# Power_Pos.net
KiCad netlist of a schematic drawn in Altium Designer
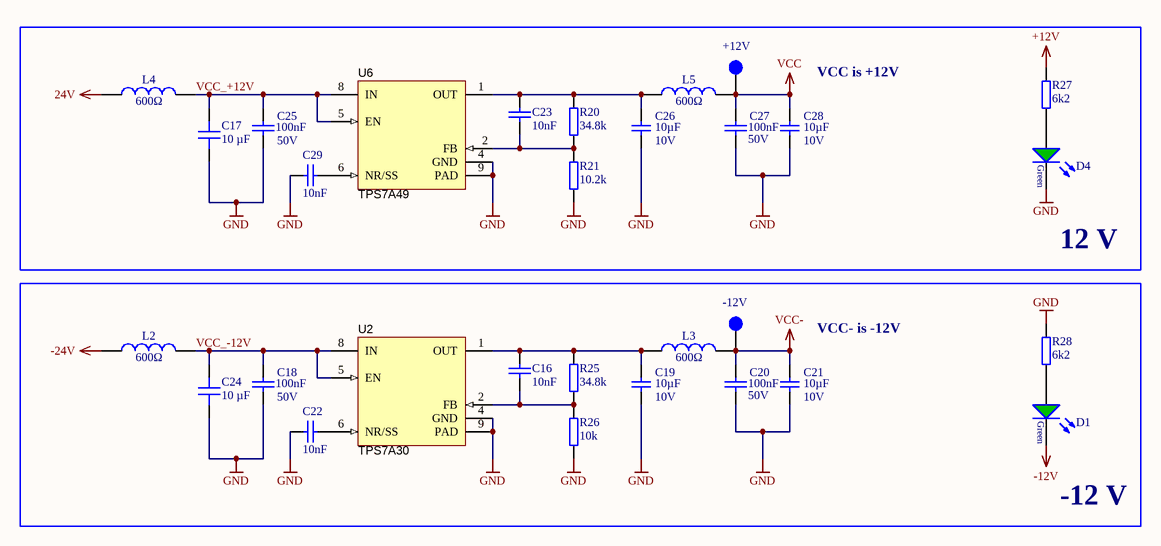
[diagram p0: Power_Pos.SchDoc]

(export (version "E")
  (design (tool "Eeschema 10.0.6"))
  (components
    (comp (ref "+12V")
      (value "VCC")
      (footprint "TP_1mm")
      (description "Testpoint 1mm")
      (fields (field (name "CREATED") "2018_06_25_AGeiger"))
      (libsource (lib "UltraZOhm_CarrierBoard") (part "TP_1mm"))
    )
    (comp (ref "-12V")
      (value "VCC")
      (footprint "TP_1mm")
      (description "Testpoint 1mm")
      (fields (field (name "CREATED") "2018_06_25_AGeiger"))
      (libsource (lib "UltraZOhm_CarrierBoard") (part "TP_1mm"))
    )
    (comp (ref "C16")
      (value "10nF")
      (footprint "CAPC1608X07N")
      (fields
        (field (name "MF") "Würth Elektronik")
        (field (name "MPN") "885012206065")
        (field (name "VOLTAGE") "25V")
      )
      (libsource (lib "UltraZohm_ADC") (part "Cap_0603"))
    )
    (comp (ref "C17")
      (value "10 µF")
      (footprint "C_1206")
      (description "Capacitor 1206, 50 VDC, 10 µF, X7R")
      (fields
        (field (name "MANUFACTURER PART NUMBER") "CGA5L1X7R1H106K160AC")
        (field (name "MANUFACTURER") "TDK")
        (field (name "CREATED FROM") "MGremer")
      )
      (libsource (lib "user") (part "Capacitor"))
    )
    (comp (ref "C18")
      (value "100nF")
      (footprint "CAPC1608X07N")
      (fields
        (field (name "MF") "Yageo")
        (field (name "MPN") "CC0603KRX7R9BB104")
        (field (name "VOLTAGE") "50V")
        (field (name "TOLERANCE") "10%")
      )
      (libsource (lib "UltraZohm_ADC") (part "Cap_0603"))
    )
    (comp (ref "C19")
      (value "10µF")
      (footprint "C_1206")
      (description "Capacitor 1206")
      (fields
        (field (name "TOLERANCE") "10%")
        (field (name "MF") "Samsung Electro-Mechanics")
        (field (name "VOLTAGE") "10V")
        (field (name "CREATED") "2020_09_17_Liegmann")
      )
      (libsource (lib "UltraZohm_ADC") (part "C_1206"))
    )
    (comp (ref "C20")
      (value "100nF")
      (footprint "CAPC1608X07N")
      (fields
        (field (name "MF") "Yageo")
        (field (name "MPN") "CC0603KRX7R9BB104")
        (field (name "VOLTAGE") "50V")
        (field (name "TOLERANCE") "10%")
      )
      (libsource (lib "UltraZohm_ADC") (part "Cap_0603"))
    )
    (comp (ref "C21")
      (value "10µF")
      (footprint "C_1206")
      (description "Capacitor 1206")
      (fields
        (field (name "TOLERANCE") "10%")
        (field (name "MF") "Samsung Electro-Mechanics")
        (field (name "VOLTAGE") "10V")
        (field (name "CREATED") "2020_09_17_Liegmann")
      )
      (libsource (lib "UltraZohm_ADC") (part "C_1206"))
    )
    (comp (ref "C22")
      (value "10nF")
      (footprint "CAPC1608X07N")
      (fields
        (field (name "MF") "Würth Elektronik")
        (field (name "MPN") "885012206065")
        (field (name "VOLTAGE") "25V")
      )
      (libsource (lib "UltraZohm_ADC") (part "Cap_0603"))
    )
    (comp (ref "C23")
      (value "10nF")
      (footprint "CAPC1608X07N")
      (fields
        (field (name "MF") "Würth Elektronik")
        (field (name "MPN") "885012206065")
        (field (name "VOLTAGE") "25V")
      )
      (libsource (lib "UltraZohm_ADC") (part "Cap_0603"))
    )
    (comp (ref "C24")
      (value "10 µF")
      (footprint "C_1206")
      (description "Capacitor 1206, 50 VDC, 10 µF, X7R")
      (fields
        (field (name "MANUFACTURER PART NUMBER") "CGA5L1X7R1H106K160AC")
        (field (name "MANUFACTURER") "TDK")
        (field (name "CREATED FROM") "MGremer")
      )
      (libsource (lib "user") (part "Capacitor"))
    )
    (comp (ref "C25")
      (value "100nF")
      (footprint "CAPC1608X07N")
      (fields
        (field (name "MF") "Yageo")
        (field (name "MPN") "CC0603KRX7R9BB104")
        (field (name "VOLTAGE") "50V")
        (field (name "TOLERANCE") "10%")
      )
      (libsource (lib "UltraZohm_ADC") (part "Cap_0603"))
    )
    (comp (ref "C26")
      (value "10µF")
      (footprint "C_1206")
      (description "Capacitor 1206")
      (fields
        (field (name "TOLERANCE") "10%")
        (field (name "MF") "Samsung Electro-Mechanics")
        (field (name "VOLTAGE") "10V")
        (field (name "CREATED") "2020_09_17_Liegmann")
      )
      (libsource (lib "UltraZohm_ADC") (part "C_1206"))
    )
    (comp (ref "C27")
      (value "100nF")
      (footprint "CAPC1608X07N")
      (fields
        (field (name "MF") "Yageo")
        (field (name "MPN") "CC0603KRX7R9BB104")
        (field (name "VOLTAGE") "50V")
        (field (name "TOLERANCE") "10%")
      )
      (libsource (lib "UltraZohm_ADC") (part "Cap_0603"))
    )
    (comp (ref "C28")
      (value "10µF")
      (footprint "C_1206")
      (description "Capacitor 1206")
      (fields
        (field (name "TOLERANCE") "10%")
        (field (name "MF") "Samsung Electro-Mechanics")
        (field (name "VOLTAGE") "10V")
        (field (name "CREATED") "2020_09_17_Liegmann")
      )
      (libsource (lib "UltraZohm_ADC") (part "C_1206"))
    )
    (comp (ref "C29")
      (value "10nF")
      (footprint "CAPC1608X07N")
      (fields
        (field (name "MF") "Würth Elektronik")
        (field (name "MPN") "885012206065")
        (field (name "VOLTAGE") "25V")
      )
      (libsource (lib "UltraZohm_ADC") (part "Cap_0603"))
    )
    (comp (ref "D1")
      (value "150060GS75000")
      (footprint "WL-SMCW_0603")
      (description "WL-SMCW SMD Mono-color Chip LED Waterclear, size 0603, Green, 3.2 V, 140°")
      (fields (field (name "MF") "Wuerth Elektronik") (field (name "CREATED") "2018_09_06_AGeiger"))
      (libsource (lib "UltraZohm_ADC") (part "LED_Green_0603"))
    )
    (comp (ref "D4")
      (value "150060GS75000")
      (footprint "WL-SMCW_0603")
      (description "WL-SMCW SMD Mono-color Chip LED Waterclear, size 0603, Green, 3.2 V, 140°")
      (fields (field (name "MF") "Wuerth Elektronik") (field (name "CREATED") "2018_09_06_AGeiger"))
      (libsource (lib "UltraZohm_ADC") (part "LED_Green_0603"))
    )
    (comp (ref "L2")
      (value "600Ω")
      (footprint "WE-CBF_0805_High Current")
      (description "WE-CBF SMD EMI Suppression Ferrite Bead, 0805, 600Ω")
      (fields (field (name "MF") "Würth Elektronik") (field (name "MPN") "742792040"))
      (libsource (lib "UltraZohm_ADC") (part "WE-CBF, 742792040"))
    )
    (comp (ref "L3")
      (value "600Ω")
      (footprint "WE-CBF_0805_High Current")
      (description "WE-CBF SMD EMI Suppression Ferrite Bead, 0805, 600Ω")
      (fields (field (name "MF") "Würth Elektronik") (field (name "MPN") "742792040"))
      (libsource (lib "UltraZohm_ADC") (part "WE-CBF, 742792040"))
    )
    (comp (ref "L4")
      (value "600Ω")
      (footprint "WE-CBF_0805_High Current")
      (description "WE-CBF SMD EMI Suppression Ferrite Bead, 0805, 600Ω")
      (fields (field (name "MF") "Würth Elektronik") (field (name "MPN") "742792040"))
      (libsource (lib "UltraZohm_ADC") (part "WE-CBF, 742792040"))
    )
    (comp (ref "L5")
      (value "600Ω")
      (footprint "WE-CBF_0805_High Current")
      (description "WE-CBF SMD EMI Suppression Ferrite Bead, 0805, 600Ω")
      (fields (field (name "MF") "Würth Elektronik") (field (name "MPN") "742792040"))
      (libsource (lib "UltraZohm_ADC") (part "WE-CBF, 742792040"))
    )
    (comp (ref "R20")
      (value "34.8k")
      (footprint "RESC1608X06N")
      (fields
        (field (name "MF") "Bourns")
        (field (name "MPN") "CR0603-FX-3482ELF")
        (field (name "TOLERANCE") "1%")
      )
      (libsource (lib "UltraZohm_ADC") (part "R_0603"))
    )
    (comp (ref "R21")
      (value "10.2k")
      (footprint "RESC1608X06N")
      (fields
        (field (name "MF") "Bourns")
        (field (name "MPN") "CR0603-FX-1022ELF")
        (field (name "TOLERANCE") "1%")
      )
      (libsource (lib "UltraZohm_ADC") (part "R_0603"))
    )
    (comp (ref "R25")
      (value "34.8k")
      (footprint "RESC1608X06N")
      (fields
        (field (name "MF") "Bourns")
        (field (name "MPN") "CR0603-FX-3482ELF")
        (field (name "TOLERANCE") "1%")
      )
      (libsource (lib "UltraZohm_ADC") (part "R_0603"))
    )
    (comp (ref "R26")
      (value "10k")
      (footprint "RESC1608X06N")
      (fields
        (field (name "MF") "Bourns")
        (field (name "MPN") "CR0603-FX-1002ELF")
        (field (name "TOLERANCE") "1%")
      )
      (libsource (lib "UltraZohm_ADC") (part "R_0603"))
    )
    (comp (ref "R27")
      (value "6k2")
      (footprint "RES 0603_1608")
      (description "SMD resistor E24 series")
      (fields
        (field (name "MANUFACTURER PART NUMBER") "RK73B1JTTD622J")
        (field (name "MANUFACTURER") "KOA Speer")
        (field (name "CREATED FROM") "MGremer")
      )
      (libsource (lib "user") (part "Resistor"))
    )
    (comp (ref "R28")
      (value "6k2")
      (footprint "RES 0603_1608")
      (description "SMD resistor E24 series")
      (fields
        (field (name "MANUFACTURER PART NUMBER") "RK73B1JTTD622J")
        (field (name "MANUFACTURER") "KOA Speer")
        (field (name "CREATED FROM") "MGremer")
      )
      (libsource (lib "user") (part "Resistor"))
    )
    (comp (ref "U2")
      (value "TPS7A30")
      (footprint "DGN0008D_N")
      (fields (field (name "MF") "Texas Instruments") (field (name "MPN") "TPS7A3001DGN"))
      (libsource (lib "UltraZohm_ADC") (part "TPS7A3001DGN"))
    )
    (comp (ref "U6")
      (value "TPS7A49")
      (footprint "DGN0008D_N")
      (description "+36V, +150mA, Ultralow-Noise, Positive LINEAR REGULATOR, DGN0008D")
      (fields (field (name "MPN") "TPS7A4901DGN") (field (name "MF") "Texas Instruments"))
      (libsource (lib "UltraZohm_ADC") (part "TPS7A4901DGN"))
    )
  )
  (nets
    (net (code "1") (name "+12V") (class "Default")
      (node (ref "R27") (pin "2") (pinfunction "2_2") (pintype "passive"))
    )
    (net (code "2") (name "-12V") (class "Default")
      (node (ref "D1") (pin "1") (pinfunction "K_1") (pintype "passive"))
    )
    (net (code "3") (name "-24V") (class "Default")
      (node (ref "L2") (pin "1") (pinfunction "1_1") (pintype "passive"))
    )
    (net (code "4") (name "/VCC_+12V") (class "Default")
      (node (ref "C17") (pin "2") (pinfunction "2_2") (pintype "passive"))
      (node (ref "C25") (pin "1") (pinfunction "1_1") (pintype "passive"))
      (node (ref "L4") (pin "2") (pinfunction "2_2") (pintype "passive"))
      (node (ref "U6") (pin "5") (pinfunction "EN_5") (pintype "input"))
      (node (ref "U6") (pin "8") (pinfunction "IN_8") (pintype "power_in"))
    )
    (net (code "5") (name "/VCC_-12V") (class "Default")
      (node (ref "C18") (pin "1") (pinfunction "1_1") (pintype "passive"))
      (node (ref "C24") (pin "2") (pinfunction "2_2") (pintype "passive"))
      (node (ref "L2") (pin "2") (pinfunction "2_2") (pintype "passive"))
      (node (ref "U2") (pin "5") (pinfunction "EN_5") (pintype "input"))
      (node (ref "U2") (pin "8") (pinfunction "IN_8") (pintype "power_in"))
    )
    (net (code "6") (name "24V") (class "Default")
      (node (ref "L4") (pin "1") (pinfunction "1_1") (pintype "passive"))
    )
    (net (code "7") (name "GND") (class "Default")
      (node (ref "C17") (pin "1") (pinfunction "1_1") (pintype "passive"))
      (node (ref "C18") (pin "2") (pinfunction "2_2") (pintype "passive"))
      (node (ref "C19") (pin "1") (pinfunction "1_1") (pintype "passive"))
      (node (ref "C20") (pin "1") (pinfunction "1_1") (pintype "passive"))
      (node (ref "C21") (pin "1") (pinfunction "1_1") (pintype "passive"))
      (node (ref "C22") (pin "2") (pinfunction "2_2") (pintype "passive"))
      (node (ref "C24") (pin "1") (pinfunction "1_1") (pintype "passive"))
      (node (ref "C25") (pin "2") (pinfunction "2_2") (pintype "passive"))
      (node (ref "C26") (pin "1") (pinfunction "1_1") (pintype "passive"))
      (node (ref "C27") (pin "1") (pinfunction "1_1") (pintype "passive"))
      (node (ref "C28") (pin "1") (pinfunction "1_1") (pintype "passive"))
      (node (ref "C29") (pin "2") (pinfunction "2_2") (pintype "passive"))
      (node (ref "D4") (pin "1") (pinfunction "K_1") (pintype "passive"))
      (node (ref "R21") (pin "2") (pintype "passive"))
      (node (ref "R26") (pin "2") (pintype "passive"))
      (node (ref "R28") (pin "2") (pinfunction "2_2") (pintype "passive"))
      (node (ref "U2") (pin "4") (pinfunction "GND_4") (pintype "power_in"))
      (node (ref "U2") (pin "9") (pinfunction "PAD_9") (pintype "passive"))
      (node (ref "U6") (pin "4") (pinfunction "GND_4") (pintype "power_in"))
      (node (ref "U6") (pin "9") (pinfunction "PAD_9") (pintype "power_in"))
    )
    (net (code "8") (name "Net-(D1-A)") (class "Default")
      (node (ref "D1") (pin "2") (pinfunction "A_2") (pintype "passive"))
      (node (ref "R28") (pin "1") (pinfunction "1_1") (pintype "passive"))
    )
    (net (code "9") (name "Net-(D4-A)") (class "Default")
      (node (ref "D4") (pin "2") (pinfunction "A_2") (pintype "passive"))
      (node (ref "R27") (pin "1") (pinfunction "1_1") (pintype "passive"))
    )
    (net (code "10") (name "Net-(U2-FB)") (class "Default")
      (node (ref "C16") (pin "2") (pinfunction "2_2") (pintype "passive"))
      (node (ref "R25") (pin "2") (pintype "passive"))
      (node (ref "R26") (pin "1") (pintype "passive"))
      (node (ref "U2") (pin "2") (pinfunction "FB_2") (pintype "input"))
    )
    (net (code "11") (name "Net-(U2-NR{slash}SS)") (class "Default")
      (node (ref "C22") (pin "1") (pinfunction "1_1") (pintype "passive"))
      (node (ref "U2") (pin "6") (pinfunction "NR/SS_6") (pintype "input"))
    )
    (net (code "12") (name "Net-(U2-OUT)") (class "Default")
      (node (ref "C16") (pin "1") (pinfunction "1_1") (pintype "passive"))
      (node (ref "C19") (pin "2") (pinfunction "2_2") (pintype "passive"))
      (node (ref "L3") (pin "1") (pinfunction "1_1") (pintype "passive"))
      (node (ref "R25") (pin "1") (pintype "passive"))
      (node (ref "U2") (pin "1") (pinfunction "OUT_1") (pintype "power_in"))
    )
    (net (code "13") (name "Net-(U6-FB)") (class "Default")
      (node (ref "C23") (pin "2") (pinfunction "2_2") (pintype "passive"))
      (node (ref "R20") (pin "2") (pintype "passive"))
      (node (ref "R21") (pin "1") (pintype "passive"))
      (node (ref "U6") (pin "2") (pinfunction "FB_2") (pintype "input"))
    )
    (net (code "14") (name "Net-(U6-NR{slash}SS)") (class "Default")
      (node (ref "C29") (pin "1") (pinfunction "1_1") (pintype "passive"))
      (node (ref "U6") (pin "6") (pinfunction "NR/SS_6") (pintype "input"))
    )
    (net (code "15") (name "Net-(U6-OUT)") (class "Default")
      (node (ref "C23") (pin "1") (pinfunction "1_1") (pintype "passive"))
      (node (ref "C26") (pin "2") (pinfunction "2_2") (pintype "passive"))
      (node (ref "L5") (pin "1") (pinfunction "1_1") (pintype "passive"))
      (node (ref "R20") (pin "1") (pintype "passive"))
      (node (ref "U6") (pin "1") (pinfunction "OUT_1") (pintype "power_in"))
    )
    (net (code "16") (name "VCC") (class "Default")
      (node (ref "+12V") (pin "1") (pintype "passive"))
      (node (ref "C27") (pin "2") (pinfunction "2_2") (pintype "passive"))
      (node (ref "C28") (pin "2") (pinfunction "2_2") (pintype "passive"))
      (node (ref "L5") (pin "2") (pinfunction "2_2") (pintype "passive"))
    )
    (net (code "17") (name "VCC-") (class "Default")
      (node (ref "-12V") (pin "1") (pintype "passive"))
      (node (ref "C20") (pin "2") (pinfunction "2_2") (pintype "passive"))
      (node (ref "C21") (pin "2") (pinfunction "2_2") (pintype "passive"))
      (node (ref "L3") (pin "2") (pinfunction "2_2") (pintype "passive"))
    )
    (net (code "18") (name "unconnected-(U2-DNC-Pad7)") (class "Default")
      (node (ref "U2") (pin "7") (pinfunction "DNC_7") (pintype "passive"))
    )
    (net (code "19") (name "unconnected-(U2-NC-Pad3)") (class "Default")
      (node (ref "U2") (pin "3") (pinfunction "NC_3") (pintype "passive"))
    )
    (net (code "20") (name "unconnected-(U6-DNC-Pad7)") (class "Default")
      (node (ref "U6") (pin "7") (pinfunction "DNC_7") (pintype "passive"))
    )
    (net (code "21") (name "unconnected-(U6-NC-Pad3)") (class "Default")
      (node (ref "U6") (pin "3") (pinfunction "NC_3") (pintype "passive"))
    )
  )
)
